# MCU.net
KiCad netlist of a schematic drawn in Altium Designer
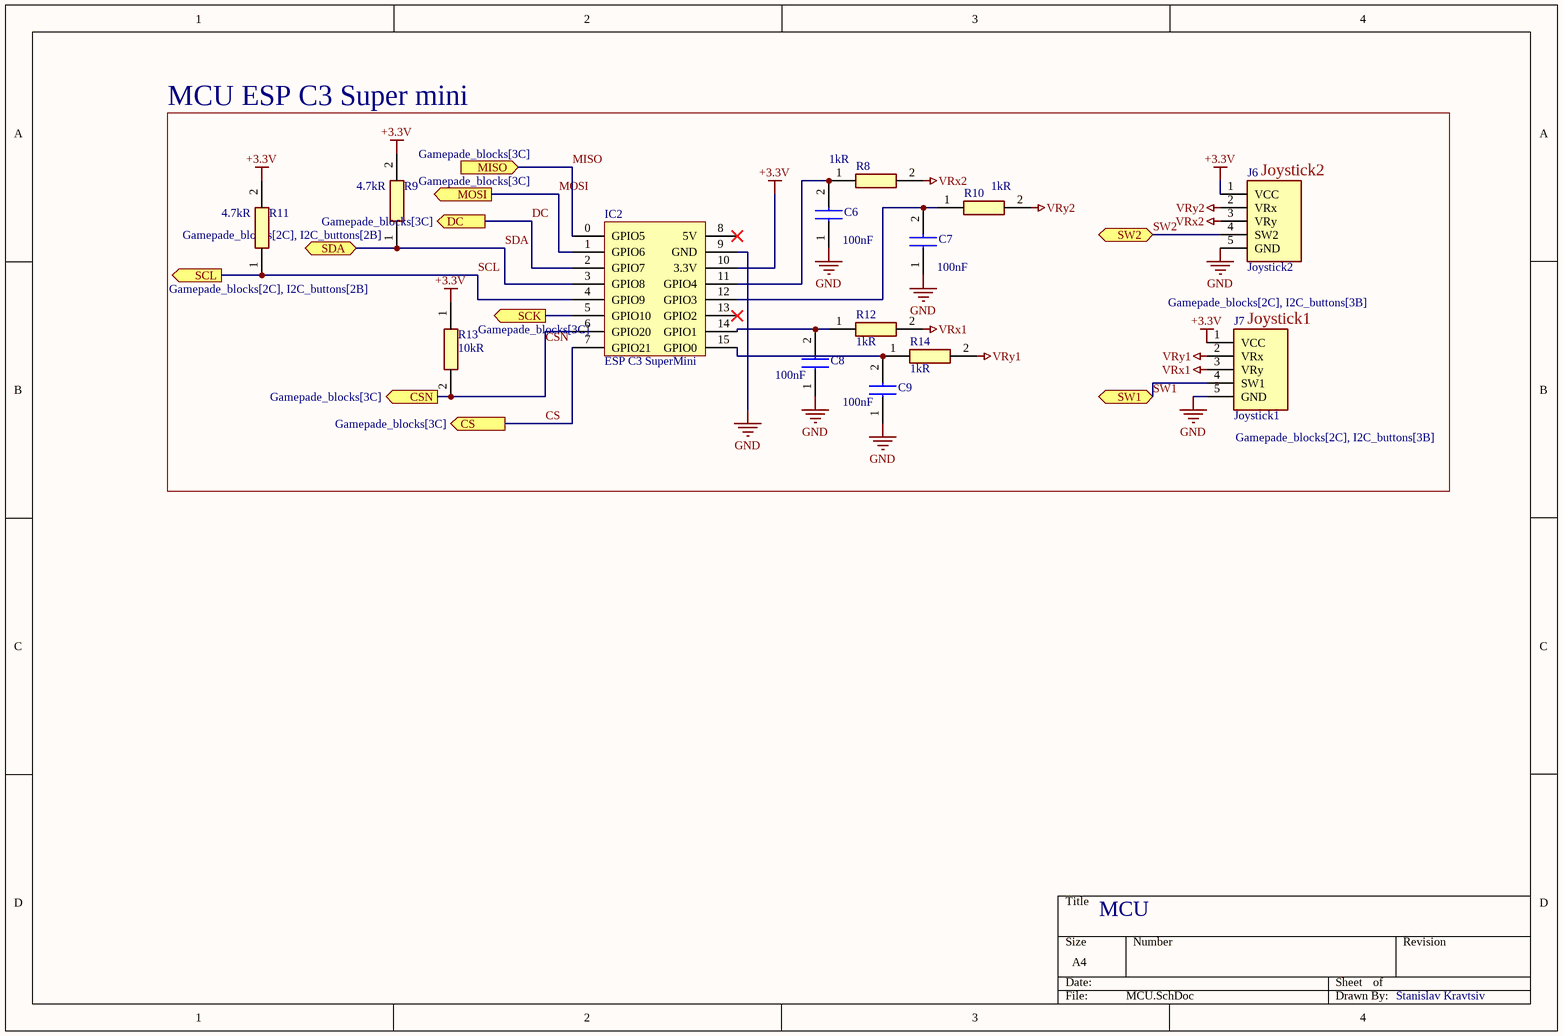
[diagram p0: MCU.SchDoc]

(export (version "E")
  (design (tool "Eeschema 10.0.6"))
  (components
    (comp (ref "C6")
      (value "100nF")
      (footprint "SamacSys:CAPC1608X95N")
      (description "Capacitor")
      (fields
        (field (name "MANUFACTURER_PART_NUMBER") "0603B104K500CT")
        (field (name "MOUSER PART NUMBER") "791-0603B104K500CT")
      )
      (libsource (lib "*") (part "0603B104K500CT"))
    )
    (comp (ref "C7")
      (value "100nF")
      (footprint "SamacSys:CAPC1608X95N")
      (description "Capacitor")
      (fields
        (field (name "MANUFACTURER_PART_NUMBER") "0603B104K500CT")
        (field (name "MOUSER PART NUMBER") "791-0603B104K500CT")
      )
      (libsource (lib "*") (part "0603B104K500CT"))
    )
    (comp (ref "C8")
      (value "100nF")
      (footprint "SamacSys:CAPC1608X95N")
      (description "Capacitor")
      (fields
        (field (name "MANUFACTURER_PART_NUMBER") "0603B104K500CT")
        (field (name "MOUSER PART NUMBER") "791-0603B104K500CT")
      )
      (libsource (lib "*") (part "0603B104K500CT"))
    )
    (comp (ref "C9")
      (value "100nF")
      (footprint "SamacSys:CAPC1608X95N")
      (description "Capacitor")
      (fields
        (field (name "MANUFACTURER_PART_NUMBER") "0603B104K500CT")
        (field (name "MOUSER PART NUMBER") "791-0603B104K500CT")
      )
      (libsource (lib "*") (part "0603B104K500CT"))
    )
    (comp (ref "IC2")
      (value "ESP C3 SuperMini")
      (footprint "esp c3 super mini")
      (libsource (lib "Gamepad_schem_lib") (part "IC"))
    )
    (comp (ref "J6")
      (value "Joystick2")
      (footprint "1.25_JSH-GH_5")
      (description "Connector")
      (fields (field (name "MANUFACTURER_PART_NUMBER") "B5B-XH-AM (LF)(SN)"))
      (libsource (lib "Gamepad_schem_lib") (part "B5B-XH-AM__LF__SN_"))
    )
    (comp (ref "J7")
      (value "Joystick1")
      (footprint "1.25_JSH-GH_5")
      (description "Connector")
      (fields (field (name "MANUFACTURER_PART_NUMBER") "B5B-XH-AM (LF)(SN)"))
      (libsource (lib "Gamepad_schem_lib") (part "B5B-XH-AM__LF__SN_"))
    )
    (comp (ref "R8")
      (value "1kR")
      (footprint "SamacSys:RESC1608X55N")
      (description "Resistor")
      (fields
        (field (name "MANUFACTURER_PART_NUMBER") "RC0603FR-071KL")
        (field (name "MOUSER PART NUMBER") "603-RC0603FR-071KL")
      )
      (libsource (lib "SamacSys") (part "RC0603FR-071KL"))
    )
    (comp (ref "R9")
      (value "4.7kR")
      (footprint "SamacSys:RESC1608X55N")
      (description "Resistor")
      (fields
        (field (name "MANUFACTURER_PART_NUMBER") "RC0603FR-074K75L")
        (field (name "MOUSER PART NUMBER") "603-RC0603FR-074K75L")
      )
      (libsource (lib "*") (part "RC0603FR-074K75L"))
    )
    (comp (ref "R10")
      (value "1kR")
      (footprint "SamacSys:RESC1608X55N")
      (description "Resistor")
      (fields
        (field (name "MANUFACTURER_PART_NUMBER") "RC0603FR-071KL")
        (field (name "MOUSER PART NUMBER") "603-RC0603FR-071KL")
      )
      (libsource (lib "SamacSys") (part "RC0603FR-071KL"))
    )
    (comp (ref "R11")
      (value "4.7kR")
      (footprint "SamacSys:RESC1608X55N")
      (description "Resistor")
      (fields
        (field (name "MANUFACTURER_PART_NUMBER") "RC0603FR-074K75L")
        (field (name "MOUSER PART NUMBER") "603-RC0603FR-074K75L")
      )
      (libsource (lib "*") (part "RC0603FR-074K75L"))
    )
    (comp (ref "R12")
      (value "1kR")
      (footprint "SamacSys:RESC1608X55N")
      (description "Resistor")
      (fields
        (field (name "MANUFACTURER_PART_NUMBER") "RC0603FR-071KL")
        (field (name "MOUSER PART NUMBER") "603-RC0603FR-071KL")
      )
      (libsource (lib "SamacSys") (part "RC0603FR-071KL"))
    )
    (comp (ref "R13")
      (value "10kR")
      (footprint "SamacSys:RESC1608X55N")
      (description "Resistor")
      (fields (field (name "MANUFACTURER_PART_NUMBER") "RC0603FR0710KL"))
      (libsource (lib "SamacSys") (part "RC0603FR0710KL"))
    )
    (comp (ref "R14")
      (value "1kR")
      (footprint "SamacSys:RESC1608X55N")
      (description "Resistor")
      (fields
        (field (name "MANUFACTURER_PART_NUMBER") "RC0603FR-071KL")
        (field (name "MOUSER PART NUMBER") "603-RC0603FR-071KL")
      )
      (libsource (lib "SamacSys") (part "RC0603FR-071KL"))
    )
  )
  (nets
    (net (code "1") (name "+3.3V") (class "Default")
      (node (ref "IC2") (pin "10") (pinfunction "3.3V_10") (pintype "passive"))
      (node (ref "J6") (pin "1") (pinfunction "VCC_1") (pintype "passive"))
      (node (ref "J7") (pin "1") (pinfunction "VCC_1") (pintype "passive"))
      (node (ref "R11") (pin "2") (pinfunction "2_2") (pintype "passive"))
      (node (ref "R13") (pin "1") (pinfunction "1_1") (pintype "passive"))
      (node (ref "R9") (pin "2") (pinfunction "2_2") (pintype "passive"))
    )
    (net (code "2") (name "/CS") (class "Default")
      (node (ref "IC2") (pin "7") (pinfunction "GPIO21_7") (pintype "passive"))
    )
    (net (code "3") (name "/CSN") (class "Default")
      (node (ref "IC2") (pin "6") (pinfunction "GPIO20_6") (pintype "passive"))
      (node (ref "R13") (pin "2") (pinfunction "2_2") (pintype "passive"))
    )
    (net (code "4") (name "/DC") (class "Default")
      (node (ref "IC2") (pin "2") (pinfunction "GPIO7_2") (pintype "passive"))
    )
    (net (code "5") (name "/MISO") (class "Default")
      (node (ref "IC2") (pin "0") (pinfunction "GPIO5_0") (pintype "passive"))
    )
    (net (code "6") (name "/MOSI") (class "Default")
      (node (ref "IC2") (pin "1") (pinfunction "GPIO6_1") (pintype "passive"))
    )
    (net (code "7") (name "/SCK") (class "Default")
      (node (ref "IC2") (pin "5") (pinfunction "GPIO10_5") (pintype "passive"))
    )
    (net (code "8") (name "/SCL") (class "Default")
      (node (ref "IC2") (pin "4") (pinfunction "GPIO9_4") (pintype "passive"))
      (node (ref "R11") (pin "1") (pinfunction "1_1") (pintype "passive"))
    )
    (net (code "9") (name "/SDA") (class "Default")
      (node (ref "IC2") (pin "3") (pinfunction "GPIO8_3") (pintype "passive"))
      (node (ref "R9") (pin "1") (pinfunction "1_1") (pintype "passive"))
    )
    (net (code "10") (name "/SW1") (class "Default")
      (node (ref "J7") (pin "4") (pinfunction "SW2_4") (pintype "passive"))
    )
    (net (code "11") (name "/SW2") (class "Default")
      (node (ref "J6") (pin "4") (pinfunction "SW2_4") (pintype "passive"))
    )
    (net (code "12") (name "GND") (class "Default")
      (node (ref "C6") (pin "1") (pinfunction "1_1") (pintype "passive"))
      (node (ref "C7") (pin "1") (pinfunction "1_1") (pintype "passive"))
      (node (ref "C8") (pin "1") (pinfunction "1_1") (pintype "passive"))
      (node (ref "C9") (pin "1") (pinfunction "1_1") (pintype "passive"))
      (node (ref "IC2") (pin "9") (pinfunction "GND_9") (pintype "passive"))
      (node (ref "J6") (pin "5") (pinfunction "GND_5") (pintype "passive"))
      (node (ref "J7") (pin "5") (pinfunction "GND_5") (pintype "passive"))
    )
    (net (code "13") (name "Net-(IC2-GPIO0)") (class "Default")
      (node (ref "C9") (pin "2") (pinfunction "2_2") (pintype "passive"))
      (node (ref "IC2") (pin "15") (pinfunction "GPIO0_15") (pintype "passive"))
      (node (ref "R14") (pin "1") (pinfunction "1_1") (pintype "passive"))
    )
    (net (code "14") (name "Net-(IC2-GPIO1)") (class "Default")
      (node (ref "C8") (pin "2") (pinfunction "2_2") (pintype "passive"))
      (node (ref "IC2") (pin "14") (pinfunction "GPIO1_14") (pintype "passive"))
      (node (ref "R12") (pin "1") (pinfunction "1_1") (pintype "passive"))
    )
    (net (code "15") (name "Net-(IC2-GPIO3)") (class "Default")
      (node (ref "C7") (pin "2") (pinfunction "2_2") (pintype "passive"))
      (node (ref "IC2") (pin "12") (pinfunction "GPIO3_12") (pintype "passive"))
      (node (ref "R10") (pin "1") (pinfunction "1_1") (pintype "passive"))
    )
    (net (code "16") (name "Net-(IC2-GPIO4)") (class "Default")
      (node (ref "C6") (pin "2") (pinfunction "2_2") (pintype "passive"))
      (node (ref "IC2") (pin "11") (pinfunction "GPIO4_11") (pintype "passive"))
      (node (ref "R8") (pin "1") (pinfunction "1_1") (pintype "passive"))
    )
    (net (code "17") (name "VRx1") (class "Default")
      (node (ref "J7") (pin "3") (pinfunction "VRy_3") (pintype "passive"))
      (node (ref "R12") (pin "2") (pinfunction "2_2") (pintype "passive"))
    )
    (net (code "18") (name "VRx2") (class "Default")
      (node (ref "J6") (pin "3") (pinfunction "VRy_3") (pintype "passive"))
      (node (ref "R8") (pin "2") (pinfunction "2_2") (pintype "passive"))
    )
    (net (code "19") (name "VRy1") (class "Default")
      (node (ref "J7") (pin "2") (pinfunction "VRx_2") (pintype "passive"))
      (node (ref "R14") (pin "2") (pinfunction "2_2") (pintype "passive"))
    )
    (net (code "20") (name "VRy2") (class "Default")
      (node (ref "J6") (pin "2") (pinfunction "VRx_2") (pintype "passive"))
      (node (ref "R10") (pin "2") (pinfunction "2_2") (pintype "passive"))
    )
    (net (code "21") (name "unconnected-(IC2-5V-Pad8)") (class "Default")
      (node (ref "IC2") (pin "8") (pinfunction "5V_8") (pintype "passive+no_connect"))
    )
    (net (code "22") (name "unconnected-(IC2-GPIO2-Pad13)") (class "Default")
      (node (ref "IC2") (pin "13") (pinfunction "GPIO2_13") (pintype "passive+no_connect"))
    )
  )
)
